# 2024_Nov_24_Esp32.net
KiCad netlist of a schematic drawn in Altium Designer
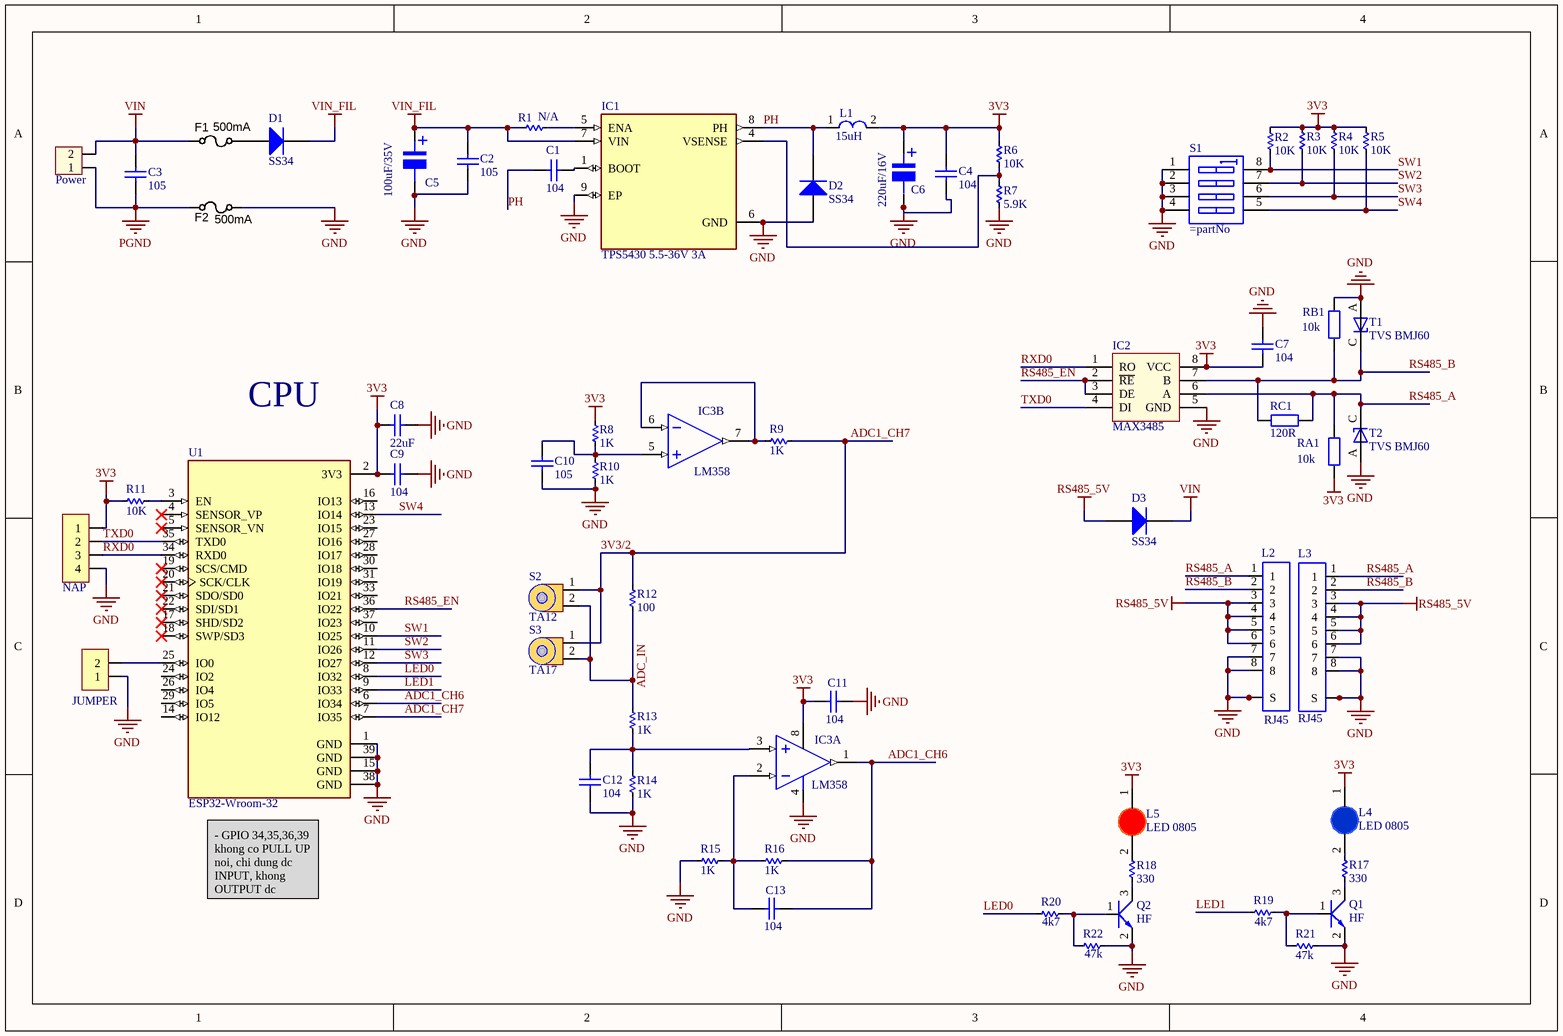
[diagram p0: 2024_Nov_24_Esp32.SchDoc]

(export (version "E")
  (design (tool "Eeschema 10.0.6"))
  (components
    (comp (ref "C1")
      (value "104")
      (footprint "tu 0805")
      (description "Dán")
      (libsource (lib "NGUYEN VAN ANH HaUI") (part "Tu 0805 105 50V 10%"))
    )
    (comp (ref "C2")
      (value "105")
      (footprint "tu 0805")
      (description "Dán")
      (libsource (lib "NGUYEN VAN ANH HaUI") (part "Tu 0805 105 50V 10%"))
    )
    (comp (ref "C3")
      (value "105")
      (footprint "tu 0805")
      (description "Dán")
      (libsource (lib "NGUYEN VAN ANH HaUI") (part "Tu 0805 105 50V 10%"))
    )
    (comp (ref "C4")
      (value "104")
      (footprint "tu 0805")
      (description "Dán")
      (libsource (lib "NGUYEN VAN ANH HaUI") (part "Tu 0805 105 50V 10%"))
    )
    (comp (ref "C5")
      (value "100uF/35V")
      (footprint "tu nhom 8 (f)")
      (description "Dán")
      (libsource (lib "NGUYEN VAN ANH HaUI") (part "Tu Nhom 100uF 50V"))
    )
    (comp (ref "C6")
      (value "220uF/16V")
      (footprint "tu nhom 6.3 (d)")
      (description "Dán")
      (libsource (lib "NGUYEN VAN ANH HaUI") (part "Tu Nhom 220uF 16V"))
    )
    (comp (ref "C7")
      (value "104")
      (footprint "tu 0805")
      (description "Dán")
      (libsource (lib "Altium_Lib_by_KhueNguyenCreator") (part "Tu 0805 104 50V 10%"))
    )
    (comp (ref "C8")
      (value "22uF")
      (footprint "tu 0805")
      (description "Dán")
      (libsource (lib "Altium_Lib_by_KhueNguyenCreator") (part "Tu 0805 105 50V 10%"))
    )
    (comp (ref "C9")
      (value "104")
      (footprint "tu 0805")
      (description "Dán")
      (libsource (lib "Altium_Lib_by_KhueNguyenCreator") (part "Tu 0805 105 50V 10%"))
    )
    (comp (ref "C10")
      (value "105")
      (footprint "tu 0805")
      (description "Dán")
      (libsource (lib "NGUYEN VAN ANH HaUI") (part "Tu 0805 105 50V 10%"))
    )
    (comp (ref "C11")
      (value "104")
      (footprint "tu 0805")
      (description "Dán")
      (libsource (lib "NGUYEN VAN ANH HaUI") (part "Tu 0805 105 50V 10%"))
    )
    (comp (ref "C12")
      (value "104")
      (footprint "tu 0805")
      (description "Dán")
      (libsource (lib "NGUYEN VAN ANH HaUI") (part "Tu 0805 105 50V 10%"))
    )
    (comp (ref "C13")
      (value "104")
      (footprint "tu 0805")
      (description "Dán")
      (libsource (lib "NGUYEN VAN ANH HaUI") (part "Tu 0805 105 50V 10%"))
    )
    (comp (ref "D1")
      (value "SS34")
      (footprint "DIODE SMA")
      (description "Dán")
      (libsource (lib "NGUYEN VAN ANH HaUI") (part "Diode SS34 ( 1N5822 )"))
    )
    (comp (ref "D2")
      (value "SS34")
      (footprint "DIODE SMA")
      (description "Dán")
      (libsource (lib "NGUYEN VAN ANH HaUI") (part "Diode SS34 ( 1N5822 )"))
    )
    (comp (ref "D3")
      (value "SS34")
      (footprint "DIODE SMA")
      (description "Dán")
      (libsource (lib "NGUYEN VAN ANH HaUI") (part "Diode SS34 ( 1N5822 )"))
    )
    (comp (ref "F1")
      (value "500mA")
      (footprint "TU 0805")
      (description "Fuse 500mA 32VDC 0603 SMD")
      (fields (field (name "Comment") "Fast Acting"))
      (libsource (lib "My library altium") (part "FUSE_FAST_500mA_0603"))
    )
    (comp (ref "F2")
      (value "500mA")
      (footprint "TU 0805")
      (description "Fuse 500mA 32VDC 0603 SMD")
      (fields (field (name "Comment") "Fast Acting"))
      (libsource (lib "My library altium") (part "FUSE_FAST_500mA_0603"))
    )
    (comp (ref "H1")
      (value "Power")
      (footprint "XH2.54M-2")
      (description "Cắm")
      (libsource (lib "NGUYEN VAN ANH HaUI") (part "Header 2P 2.54 Duc Thang"))
    )
    (comp (ref "IC1")
      (value "TPS5430 5.5-36V 3A")
      (footprint "TPS5430")
      (libsource (lib "NGUYEN VAN ANH HaUI") (part "TPS5430"))
    )
    (comp (ref "IC2")
      (value "MAX3485")
      (footprint "SOp 8")
      (description "RS232 - RS485 (Same sn75176)")
      (libsource (lib "NGUYEN VAN ANH HaUI") (part "MAX485"))
    )
    (comp (ref "IC3")
      (value "LM358")
      (footprint "SO8")
      (description "Low-Power Dual Operational Amplifier")
      (libsource (lib "NGUYEN VAN ANH HaUI") (part "LM358"))
    )
    (comp (ref "JP1")
      (value "NAP")
      (footprint "JP 1x4 DT")
      (description "Cắm")
      (libsource (lib "NGUYEN VAN ANH HaUI") (part "JP 1x4 2.54 Duc Thang"))
    )
    (comp (ref "JP2")
      (value "JUMPER")
      (footprint "JP 1x2 DT")
      (description "Cắm")
      (libsource (lib "NGUYEN VAN ANH HaUI") (part "JP 1x2 2.54 Duc Thang"))
    )
    (comp (ref "L1")
      (value "15uH")
      (footprint "L-SMD-M-7.3x4.5")
      (fields
        (field (name "PARTNO") "78477010")
        (field (name "MANUFACTURER") "Wurth Elektronik")
        (field (name "CREATED BY") "Baojun Chen")
      )
      (libsource (lib "NGUYEN VAN ANH HaUI") (part "L-SMD-1"))
    )
    (comp (ref "L2")
      (value "RJ45")
      (footprint "Ethernet HR911105A")
      (libsource (lib "NGUYEN VAN ANH HaUI") (part "Ethernet-LAN"))
    )
    (comp (ref "L3")
      (value "RJ45")
      (footprint "Ethernet HR911105A")
      (libsource (lib "NGUYEN VAN ANH HaUI") (part "Ethernet-LAN"))
    )
    (comp (ref "L4")
      (value "LED 0805")
      (footprint "LED-0805-Blue")
      (description "Dán")
      (libsource (lib "NGUYEN VAN ANH HaUI") (part "LED 0805 Xanh Duong"))
    )
    (comp (ref "L5")
      (value "LED 0805")
      (footprint "LED-0805-Red")
      (description "Dán")
      (libsource (lib "NGUYEN VAN ANH HaUI") (part "LED 0805 Do"))
    )
    (comp (ref "Q1")
      (value "HF")
      (footprint "SOT23")
      (description "NPN transistor")
      (libsource (lib "NGUYEN VAN ANH HaUI") (part "C1815 HF SMD"))
    )
    (comp (ref "Q2")
      (value "HF")
      (footprint "SOT23")
      (description "NPN transistor")
      (libsource (lib "NGUYEN VAN ANH HaUI") (part "C1815 HF SMD"))
    )
    (comp (ref "R1")
      (value "N/A")
      (footprint "RES-SMD-0805")
      (description "Resistor")
      (fields
        (field (name "MANUFACTURER") "Generic Components")
        (field (name "PUBLISHER") "Altium Hobart Technology Centre")
      )
      (libsource (lib "NGUYEN VAN ANH HaUI") (part "Res-SMD"))
    )
    (comp (ref "R2")
      (value "10K")
      (footprint "RES-SMD-0805")
      (description "Resistor")
      (fields
        (field (name "MANUFACTURER") "Generic Components")
        (field (name "PUBLISHER") "Altium Hobart Technology Centre")
      )
      (libsource (lib "NGUYEN VAN ANH HaUI") (part "Res-SMD"))
    )
    (comp (ref "R3")
      (value "10K")
      (footprint "RES-SMD-0805")
      (description "Resistor")
      (fields
        (field (name "MANUFACTURER") "Generic Components")
        (field (name "PUBLISHER") "Altium Hobart Technology Centre")
      )
      (libsource (lib "NGUYEN VAN ANH HaUI") (part "Res-SMD"))
    )
    (comp (ref "R4")
      (value "10K")
      (footprint "RES-SMD-0805")
      (description "Resistor")
      (fields
        (field (name "MANUFACTURER") "Generic Components")
        (field (name "PUBLISHER") "Altium Hobart Technology Centre")
      )
      (libsource (lib "NGUYEN VAN ANH HaUI") (part "Res-SMD"))
    )
    (comp (ref "R5")
      (value "10K")
      (footprint "RES-SMD-0805")
      (description "Resistor")
      (fields
        (field (name "MANUFACTURER") "Generic Components")
        (field (name "PUBLISHER") "Altium Hobart Technology Centre")
      )
      (libsource (lib "NGUYEN VAN ANH HaUI") (part "Res-SMD"))
    )
    (comp (ref "R6")
      (value "10K")
      (footprint "RES-SMD-0805")
      (description "Resistor")
      (fields
        (field (name "MANUFACTURER") "Generic Components")
        (field (name "PUBLISHER") "Altium Hobart Technology Centre")
      )
      (libsource (lib "NGUYEN VAN ANH HaUI") (part "Res-SMD"))
    )
    (comp (ref "R7")
      (value "5.9K")
      (footprint "RES-SMD-0805")
      (description "Resistor")
      (fields
        (field (name "MANUFACTURER") "Generic Components")
        (field (name "PUBLISHER") "Altium Hobart Technology Centre")
      )
      (libsource (lib "NGUYEN VAN ANH HaUI") (part "Res-SMD"))
    )
    (comp (ref "R8")
      (value "1K")
      (footprint "RES-SMD-0805")
      (description "Resistor")
      (fields
        (field (name "MANUFACTURER") "Generic Components")
        (field (name "PUBLISHER") "Altium Hobart Technology Centre")
      )
      (libsource (lib "NGUYEN VAN ANH HaUI") (part "Res-SMD"))
    )
    (comp (ref "R9")
      (value "1K")
      (footprint "RES-SMD-0805")
      (description "Resistor")
      (fields
        (field (name "MANUFACTURER") "Generic Components")
        (field (name "PUBLISHER") "Altium Hobart Technology Centre")
      )
      (libsource (lib "NGUYEN VAN ANH HaUI") (part "Res-SMD"))
    )
    (comp (ref "R10")
      (value "1K")
      (footprint "RES-SMD-0805")
      (description "Resistor")
      (fields
        (field (name "MANUFACTURER") "Generic Components")
        (field (name "PUBLISHER") "Altium Hobart Technology Centre")
      )
      (libsource (lib "NGUYEN VAN ANH HaUI") (part "Res-SMD"))
    )
    (comp (ref "R11")
      (value "10K")
      (footprint "RES-SMD-0805")
      (description "Resistor")
      (fields
        (field (name "MANUFACTURER") "Generic Components")
        (field (name "PUBLISHER") "Altium Hobart Technology Centre")
      )
      (libsource (lib "NGUYEN VAN ANH HaUI") (part "Res-SMD"))
    )
    (comp (ref "R12")
      (value "100")
      (footprint "RES-SMD-0805")
      (description "Resistor")
      (fields
        (field (name "MANUFACTURER") "Generic Components")
        (field (name "PUBLISHER") "Altium Hobart Technology Centre")
      )
      (libsource (lib "NGUYEN VAN ANH HaUI") (part "Res-SMD"))
    )
    (comp (ref "R13")
      (value "1K")
      (footprint "RES-SMD-0805")
      (description "Resistor")
      (fields
        (field (name "MANUFACTURER") "Generic Components")
        (field (name "PUBLISHER") "Altium Hobart Technology Centre")
      )
      (libsource (lib "NGUYEN VAN ANH HaUI") (part "Res-SMD"))
    )
    (comp (ref "R14")
      (value "1K")
      (footprint "RES-SMD-0805")
      (description "Resistor")
      (fields
        (field (name "MANUFACTURER") "Generic Components")
        (field (name "PUBLISHER") "Altium Hobart Technology Centre")
      )
      (libsource (lib "NGUYEN VAN ANH HaUI") (part "Res-SMD"))
    )
    (comp (ref "R15")
      (value "1K")
      (footprint "RES-SMD-0805")
      (description "Resistor")
      (fields
        (field (name "MANUFACTURER") "Generic Components")
        (field (name "PUBLISHER") "Altium Hobart Technology Centre")
      )
      (libsource (lib "NGUYEN VAN ANH HaUI") (part "Res-SMD"))
    )
    (comp (ref "R16")
      (value "1K")
      (footprint "RES-SMD-0805")
      (description "Resistor")
      (fields
        (field (name "MANUFACTURER") "Generic Components")
        (field (name "PUBLISHER") "Altium Hobart Technology Centre")
      )
      (libsource (lib "NGUYEN VAN ANH HaUI") (part "Res-SMD"))
    )
    (comp (ref "R17")
      (value "330")
      (footprint "RES-SMD-0805")
      (description "Resistor")
      (fields
        (field (name "MANUFACTURER") "Generic Components")
        (field (name "PUBLISHER") "Altium Hobart Technology Centre")
      )
      (libsource (lib "NGUYEN VAN ANH HaUI") (part "Res-SMD"))
    )
    (comp (ref "R18")
      (value "330")
      (footprint "RES-SMD-0805")
      (description "Resistor")
      (fields
        (field (name "MANUFACTURER") "Generic Components")
        (field (name "PUBLISHER") "Altium Hobart Technology Centre")
      )
      (libsource (lib "NGUYEN VAN ANH HaUI") (part "Res-SMD"))
    )
    (comp (ref "R19")
      (value "4k7")
      (footprint "RES-SMD-0805")
      (description "Resistor")
      (fields
        (field (name "MANUFACTURER") "Generic Components")
        (field (name "PUBLISHER") "Altium Hobart Technology Centre")
      )
      (libsource (lib "NGUYEN VAN ANH HaUI") (part "Res-SMD"))
    )
    (comp (ref "R20")
      (value "4k7")
      (footprint "RES-SMD-0805")
      (description "Resistor")
      (fields
        (field (name "MANUFACTURER") "Generic Components")
        (field (name "PUBLISHER") "Altium Hobart Technology Centre")
      )
      (libsource (lib "NGUYEN VAN ANH HaUI") (part "Res-SMD"))
    )
    (comp (ref "R21")
      (value "47k")
      (footprint "RES-SMD-0805")
      (description "Resistor")
      (fields
        (field (name "MANUFACTURER") "Generic Components")
        (field (name "PUBLISHER") "Altium Hobart Technology Centre")
      )
      (libsource (lib "NGUYEN VAN ANH HaUI") (part "Res-SMD"))
    )
    (comp (ref "R22")
      (value "47k")
      (footprint "RES-SMD-0805")
      (description "Resistor")
      (fields
        (field (name "MANUFACTURER") "Generic Components")
        (field (name "PUBLISHER") "Altium Hobart Technology Centre")
      )
      (libsource (lib "NGUYEN VAN ANH HaUI") (part "Res-SMD"))
    )
    (comp (ref "RA1")
      (value "10k")
      (footprint "SM-RES-0805")
      (description "Resistor 1/4W")
      (libsource (lib "syhaunguyen") (part "R1/4W"))
    )
    (comp (ref "RB1")
      (value "10k")
      (footprint "SM-RES-0805")
      (description "Resistor 1/4W")
      (libsource (lib "syhaunguyen") (part "R1/4W"))
    )
    (comp (ref "RC1")
      (value "120R")
      (footprint "SM-RES-0805")
      (description "Resistor 1/4W")
      (libsource (lib "syhaunguyen") (part "R1/4W"))
    )
    (comp (ref "S1")
      (value "~")
      (footprint "SW-DIP4")
      (description "WS-DITV 2.54 mm small compact THT flat actuator with top tape")
      (fields
        (field (name "MANUFACTURER") "Wurth Elektronik")
        (field (name "PART NO.") "418127160904")
        (field (name "CREATED BY") "Baojun Chen")
      )
      (libsource (lib "NGUYEN VAN ANH HaUI") (part "SWDIP4"))
    )
    (comp (ref "S2") (value "TA12") (footprint "TA12") (libsource (lib "NGUYEN VAN ANH HaUI") (part "TA12")))
    (comp (ref "S3") (value "TA17") (footprint "TA12") (libsource (lib "NGUYEN VAN ANH HaUI") (part "TA12")))
    (comp (ref "T1")
      (value "TVS BMJ60")
      (footprint "TVS BMJ60")
      (libsource (lib "NGUYEN VAN ANH HaUI") (part "TVS BMJ60"))
    )
    (comp (ref "T2")
      (value "TVS BMJ60")
      (footprint "TVS BMJ60")
      (libsource (lib "NGUYEN VAN ANH HaUI") (part "TVS BMJ60"))
    )
    (comp (ref "U1")
      (value "ESP32-Wroom-32")
      (footprint "ESP32-Wroom-32")
      (libsource (lib "NGUYEN VAN ANH HaUI") (part "ESP32-Wroom-32"))
    )
  )
  (nets
    (net (code "1") (name "/3V3{slash}2") (class "Default")
      (node (ref "R12") (pin "1") (pinfunction "1_1") (pintype "passive"))
      (node (ref "R9") (pin "2") (pinfunction "2_2") (pintype "passive"))
      (node (ref "S2") (pin "1") (pinfunction "0_1") (pintype "passive"))
      (node (ref "S3") (pin "1") (pinfunction "0_1") (pintype "passive"))
      (node (ref "U1") (pin "7") (pinfunction "IO35_7") (pintype "bidirectional"))
    )
    (net (code "2") (name "/ADC1_CH6") (class "Default")
      (node (ref "C13") (pin "1") (pinfunction "1_1") (pintype "passive"))
      (node (ref "IC3") (pin "1") (pinfunction "OUT_1") (pintype "output"))
      (node (ref "R16") (pin "2") (pinfunction "2_2") (pintype "passive"))
      (node (ref "U1") (pin "6") (pinfunction "IO34_6") (pintype "bidirectional"))
    )
    (net (code "3") (name "/ADC_IN") (class "Default")
      (node (ref "R12") (pin "2") (pinfunction "2_2") (pintype "passive"))
      (node (ref "R13") (pin "1") (pinfunction "1_1") (pintype "passive"))
      (node (ref "S2") (pin "2") (pinfunction "1_2") (pintype "passive"))
      (node (ref "S3") (pin "2") (pinfunction "1_2") (pintype "passive"))
    )
    (net (code "4") (name "/LED0") (class "Default")
      (node (ref "R20") (pin "2") (pinfunction "2_2") (pintype "passive"))
      (node (ref "U1") (pin "8") (pinfunction "IO32_8") (pintype "bidirectional"))
    )
    (net (code "5") (name "/LED1") (class "Default")
      (node (ref "R19") (pin "2") (pinfunction "2_2") (pintype "passive"))
      (node (ref "U1") (pin "9") (pinfunction "IO33_9") (pintype "bidirectional"))
    )
    (net (code "6") (name "/PH") (class "Default")
      (node (ref "C1") (pin "1") (pinfunction "1_1") (pintype "passive"))
      (node (ref "D2") (pin "2") (pinfunction "K_2") (pintype "passive"))
      (node (ref "IC1") (pin "8") (pinfunction "PH_8") (pintype "output"))
      (node (ref "L1") (pin "1") (pinfunction "1_1") (pintype "passive"))
    )
    (net (code "7") (name "/RS485_A") (class "Default")
      (node (ref "IC2") (pin "6") (pinfunction "A_6") (pintype "passive"))
      (node (ref "L2") (pin "1") (pinfunction "1_1") (pintype "passive"))
      (node (ref "L3") (pin "1") (pinfunction "1_1") (pintype "passive"))
      (node (ref "RA1") (pin "2") (pinfunction "2_2") (pintype "passive"))
      (node (ref "RC1") (pin "1") (pinfunction "1_1") (pintype "passive"))
      (node (ref "T2") (pin "C") (pinfunction "C_C") (pintype "passive"))
    )
    (net (code "8") (name "/RS485_B") (class "Default")
      (node (ref "IC2") (pin "7") (pinfunction "B_7") (pintype "passive"))
      (node (ref "L2") (pin "2") (pinfunction "2_2") (pintype "passive"))
      (node (ref "L3") (pin "2") (pinfunction "2_2") (pintype "passive"))
      (node (ref "RB1") (pin "1") (pinfunction "1_1") (pintype "passive"))
      (node (ref "RC1") (pin "2") (pinfunction "2_2") (pintype "passive"))
      (node (ref "T1") (pin "C") (pinfunction "C_C") (pintype "passive"))
    )
    (net (code "9") (name "/RS485_EN") (class "Default")
      (node (ref "IC2") (pin "2") (pinfunction "~{RE}_2") (pintype "passive"))
      (node (ref "IC2") (pin "3") (pinfunction "DE_3") (pintype "passive"))
      (node (ref "U1") (pin "36") (pinfunction "IO22_36") (pintype "bidirectional"))
    )
    (net (code "10") (name "/RXD0") (class "Default")
      (node (ref "IC2") (pin "1") (pinfunction "RO_1") (pintype "passive"))
      (node (ref "JP1") (pin "3") (pinfunction "3_3") (pintype "passive"))
      (node (ref "U1") (pin "34") (pinfunction "RXD0_34") (pintype "bidirectional"))
    )
    (net (code "11") (name "/SW1") (class "Default")
      (node (ref "R2") (pin "1") (pinfunction "1_1") (pintype "passive"))
      (node (ref "S1") (pin "8") (pinfunction "8_8") (pintype "passive"))
      (node (ref "U1") (pin "10") (pinfunction "IO25_10") (pintype "bidirectional"))
    )
    (net (code "12") (name "/SW2") (class "Default")
      (node (ref "R3") (pin "1") (pinfunction "1_1") (pintype "passive"))
      (node (ref "S1") (pin "7") (pinfunction "7_7") (pintype "passive"))
      (node (ref "U1") (pin "11") (pinfunction "IO26_11") (pintype "bidirectional"))
    )
    (net (code "13") (name "/SW3") (class "Default")
      (node (ref "R4") (pin "1") (pinfunction "1_1") (pintype "passive"))
      (node (ref "S1") (pin "6") (pinfunction "6_6") (pintype "passive"))
      (node (ref "U1") (pin "12") (pinfunction "IO27_12") (pintype "bidirectional"))
    )
    (net (code "14") (name "/SW4") (class "Default")
      (node (ref "R5") (pin "1") (pinfunction "1_1") (pintype "passive"))
      (node (ref "S1") (pin "5") (pinfunction "5_5") (pintype "passive"))
      (node (ref "U1") (pin "13") (pinfunction "IO14_13") (pintype "bidirectional"))
    )
    (net (code "15") (name "/TXD0") (class "Default")
      (node (ref "IC2") (pin "4") (pinfunction "DI_4") (pintype "passive"))
      (node (ref "JP1") (pin "2") (pinfunction "2_2") (pintype "passive"))
      (node (ref "U1") (pin "35") (pinfunction "TXD0_35") (pintype "bidirectional"))
    )
    (net (code "16") (name "3V3") (class "Default")
      (node (ref "C11") (pin "2") (pinfunction "2_2") (pintype "passive"))
      (node (ref "C4") (pin "2") (pinfunction "2_2") (pintype "passive"))
      (node (ref "C6") (pin "1") (pinfunction "1_1") (pintype "passive"))
      (node (ref "C7") (pin "1") (pinfunction "1_1") (pintype "passive"))
      (node (ref "C8") (pin "2") (pinfunction "2_2") (pintype "passive"))
      (node (ref "C9") (pin "2") (pinfunction "2_2") (pintype "passive"))
      (node (ref "IC2") (pin "8") (pinfunction "VCC_8") (pintype "passive"))
      (node (ref "IC3") (pin "8") (pinfunction "+V_8") (pintype "passive"))
      (node (ref "JP1") (pin "1") (pinfunction "1_1") (pintype "passive"))
      (node (ref "L1") (pin "2") (pinfunction "2_2") (pintype "passive"))
      (node (ref "L4") (pin "1") (pinfunction "A_1") (pintype "passive"))
      (node (ref "L5") (pin "1") (pinfunction "A_1") (pintype "passive"))
      (node (ref "R11") (pin "1") (pinfunction "1_1") (pintype "passive"))
      (node (ref "R2") (pin "2") (pinfunction "2_2") (pintype "passive"))
      (node (ref "R3") (pin "2") (pinfunction "2_2") (pintype "passive"))
      (node (ref "R4") (pin "2") (pinfunction "2_2") (pintype "passive"))
      (node (ref "R5") (pin "2") (pinfunction "2_2") (pintype "passive"))
      (node (ref "R6") (pin "1") (pinfunction "1_1") (pintype "passive"))
      (node (ref "R8") (pin "1") (pinfunction "1_1") (pintype "passive"))
      (node (ref "RA1") (pin "1") (pinfunction "1_1") (pintype "passive"))
      (node (ref "U1") (pin "2") (pinfunction "3V3_2") (pintype "power_in"))
    )
    (net (code "17") (name "GND") (class "Default")
      (node (ref "C10") (pin "2") (pinfunction "2_2") (pintype "passive"))
      (node (ref "C11") (pin "1") (pinfunction "1_1") (pintype "passive"))
      (node (ref "C12") (pin "1") (pinfunction "1_1") (pintype "passive"))
      (node (ref "C2") (pin "2") (pinfunction "2_2") (pintype "passive"))
      (node (ref "C4") (pin "1") (pinfunction "1_1") (pintype "passive"))
      (node (ref "C5") (pin "2") (pinfunction "2_2") (pintype "passive"))
      (node (ref "C6") (pin "2") (pinfunction "2_2") (pintype "passive"))
      (node (ref "C7") (pin "2") (pinfunction "2_2") (pintype "passive"))
      (node (ref "C8") (pin "1") (pinfunction "1_1") (pintype "passive"))
      (node (ref "C9") (pin "1") (pinfunction "1_1") (pintype "passive"))
      (node (ref "D2") (pin "1") (pinfunction "A_1") (pintype "passive"))
      (node (ref "F2") (pin "2") (pinfunction "2_2") (pintype "passive"))
      (node (ref "IC1") (pin "6") (pinfunction "GND_6") (pintype "power_in"))
      (node (ref "IC1") (pin "9") (pinfunction "EP_9") (pintype "bidirectional"))
      (node (ref "IC2") (pin "5") (pinfunction "GND_5") (pintype "passive"))
      (node (ref "IC3") (pin "4") (pinfunction "-V_4") (pintype "passive"))
      (node (ref "JP1") (pin "4") (pinfunction "4_4") (pintype "passive"))
      (node (ref "JP2") (pin "1") (pinfunction "1_1") (pintype "passive"))
      (node (ref "L2") (pin "7") (pinfunction "7_7") (pintype "passive"))
      (node (ref "L2") (pin "8") (pinfunction "8_8") (pintype "passive"))
      (node (ref "L2") (pin "S1") (pinfunction "S_S1") (pintype "passive"))
      (node (ref "L2") (pin "S2") (pinfunction "S_S2") (pintype "passive"))
      (node (ref "L3") (pin "7") (pinfunction "7_7") (pintype "passive"))
      (node (ref "L3") (pin "8") (pinfunction "8_8") (pintype "passive"))
      (node (ref "L3") (pin "S1") (pinfunction "S_S1") (pintype "passive"))
      (node (ref "L3") (pin "S2") (pinfunction "S_S2") (pintype "passive"))
      (node (ref "Q1") (pin "2") (pinfunction "E_2") (pintype "passive"))
      (node (ref "Q2") (pin "2") (pinfunction "E_2") (pintype "passive"))
      (node (ref "R10") (pin "2") (pinfunction "2_2") (pintype "passive"))
      (node (ref "R14") (pin "2") (pinfunction "2_2") (pintype "passive"))
      (node (ref "R15") (pin "1") (pinfunction "1_1") (pintype "passive"))
      (node (ref "R21") (pin "1") (pinfunction "1_1") (pintype "passive"))
      (node (ref "R22") (pin "1") (pinfunction "1_1") (pintype "passive"))
      (node (ref "R7") (pin "2") (pinfunction "2_2") (pintype "passive"))
      (node (ref "RB1") (pin "2") (pinfunction "2_2") (pintype "passive"))
      (node (ref "S1") (pin "1") (pinfunction "1_1") (pintype "passive"))
      (node (ref "S1") (pin "2") (pinfunction "2_2") (pintype "passive"))
      (node (ref "S1") (pin "3") (pinfunction "3_3") (pintype "passive"))
      (node (ref "S1") (pin "4") (pinfunction "4_4") (pintype "passive"))
      (node (ref "T1") (pin "A") (pinfunction "A_A") (pintype "passive"))
      (node (ref "T2") (pin "A") (pinfunction "A_A") (pintype "passive"))
      (node (ref "U1") (pin "1") (pinfunction "GND_1") (pintype "power_in"))
      (node (ref "U1") (pin "15") (pinfunction "GND_15") (pintype "power_in"))
      (node (ref "U1") (pin "38") (pinfunction "GND_38") (pintype "power_in"))
      (node (ref "U1") (pin "39") (pinfunction "GND_39") (pintype "power_in"))
    )
    (net (code "18") (name "Net-(D1-A)") (class "Default")
      (node (ref "D1") (pin "1") (pinfunction "A_1") (pintype "passive"))
      (node (ref "F1") (pin "2") (pinfunction "2_2") (pintype "passive"))
    )
    (net (code "19") (name "Net-(IC1-BOOT)") (class "Default")
      (node (ref "C1") (pin "2") (pinfunction "2_2") (pintype "passive"))
      (node (ref "IC1") (pin "1") (pinfunction "BOOT_1") (pintype "bidirectional"))
    )
    (net (code "20") (name "Net-(IC1-ENA)") (class "Default")
      (node (ref "IC1") (pin "5") (pinfunction "ENA_5") (pintype "input"))
      (node (ref "R1") (pin "1") (pinfunction "1_1") (pintype "passive"))
    )
    (net (code "21") (name "Net-(IC1-VSENSE)") (class "Default")
      (node (ref "IC1") (pin "4") (pinfunction "VSENSE_4") (pintype "output"))
      (node (ref "R6") (pin "2") (pinfunction "2_2") (pintype "passive"))
      (node (ref "R7") (pin "1") (pinfunction "1_1") (pintype "passive"))
    )
    (net (code "22") (name "Net-(IC3A-IN+)") (class "Default")
      (node (ref "C12") (pin "2") (pinfunction "2_2") (pintype "passive"))
      (node (ref "IC3") (pin "3") (pinfunction "IN+_3") (pintype "input"))
      (node (ref "R13") (pin "2") (pinfunction "2_2") (pintype "passive"))
      (node (ref "R14") (pin "1") (pinfunction "1_1") (pintype "passive"))
    )
    (net (code "23") (name "Net-(IC3A-IN-)") (class "Default")
      (node (ref "C13") (pin "2") (pinfunction "2_2") (pintype "passive"))
      (node (ref "IC3") (pin "2") (pinfunction "IN-_2") (pintype "input"))
      (node (ref "R15") (pin "2") (pinfunction "2_2") (pintype "passive"))
      (node (ref "R16") (pin "1") (pinfunction "1_1") (pintype "passive"))
    )
    (net (code "24") (name "Net-(IC3B-IN+)") (class "Default")
      (node (ref "C10") (pin "1") (pinfunction "1_1") (pintype "passive"))
      (node (ref "IC3") (pin "5") (pinfunction "IN+_5") (pintype "input"))
      (node (ref "R10") (pin "1") (pinfunction "1_1") (pintype "passive"))
      (node (ref "R8") (pin "2") (pinfunction "2_2") (pintype "passive"))
    )
    (net (code "25") (name "Net-(IC3B-IN-)") (class "Default")
      (node (ref "IC3") (pin "6") (pinfunction "IN-_6") (pintype "input"))
      (node (ref "IC3") (pin "7") (pinfunction "OUT_7") (pintype "output"))
      (node (ref "R9") (pin "1") (pinfunction "1_1") (pintype "passive"))
    )
    (net (code "26") (name "Net-(L4-K)") (class "Default")
      (node (ref "L4") (pin "2") (pinfunction "K_2") (pintype "passive"))
      (node (ref "R17") (pin "2") (pinfunction "2_2") (pintype "passive"))
    )
    (net (code "27") (name "Net-(L5-K)") (class "Default")
      (node (ref "L5") (pin "2") (pinfunction "K_2") (pintype "passive"))
      (node (ref "R18") (pin "2") (pinfunction "2_2") (pintype "passive"))
    )
    (net (code "28") (name "Net-(Q1-B)") (class "Default")
      (node (ref "Q1") (pin "1") (pinfunction "B_1") (pintype "passive"))
      (node (ref "R19") (pin "1") (pinfunction "1_1") (pintype "passive"))
      (node (ref "R21") (pin "2") (pinfunction "2_2") (pintype "passive"))
    )
    (net (code "29") (name "Net-(Q1-C)") (class "Default")
      (node (ref "Q1") (pin "3") (pinfunction "C_3") (pintype "passive"))
      (node (ref "R17") (pin "1") (pinfunction "1_1") (pintype "passive"))
    )
    (net (code "30") (name "Net-(Q2-B)") (class "Default")
      (node (ref "Q2") (pin "1") (pinfunction "B_1") (pintype "passive"))
      (node (ref "R20") (pin "1") (pinfunction "1_1") (pintype "passive"))
      (node (ref "R22") (pin "2") (pinfunction "2_2") (pintype "passive"))
    )
    (net (code "31") (name "Net-(Q2-C)") (class "Default")
      (node (ref "Q2") (pin "3") (pinfunction "C_3") (pintype "passive"))
      (node (ref "R18") (pin "1") (pinfunction "1_1") (pintype "passive"))
    )
    (net (code "32") (name "Net-(U1-EN)") (class "Default")
      (node (ref "R11") (pin "2") (pinfunction "2_2") (pintype "passive"))
      (node (ref "U1") (pin "3") (pinfunction "EN_3") (pintype "input"))
    )
    (net (code "33") (name "Net-(U1-IO0)") (class "Default")
      (node (ref "JP2") (pin "2") (pinfunction "2_2") (pintype "passive"))
      (node (ref "U1") (pin "25") (pinfunction "IO0_25") (pintype "bidirectional"))
    )
    (net (code "34") (name "PGND") (class "Default")
      (node (ref "C3") (pin "2") (pinfunction "2_2") (pintype "passive"))
      (node (ref "F2") (pin "1") (pinfunction "1_1") (pintype "passive"))
      (node (ref "H1") (pin "1") (pinfunction "1_1") (pintype "passive"))
    )
    (net (code "35") (name "RS485_5V") (class "Default")
      (node (ref "D3") (pin "1") (pinfunction "A_1") (pintype "passive"))
      (node (ref "L2") (pin "3") (pinfunction "3_3") (pintype "passive"))
      (node (ref "L2") (pin "4") (pinfunction "4_4") (pintype "passive"))
      (node (ref "L2") (pin "5") (pinfunction "5_5") (pintype "passive"))
      (node (ref "L2") (pin "6") (pinfunction "6_6") (pintype "passive"))
      (node (ref "L3") (pin "3") (pinfunction "3_3") (pintype "passive"))
      (node (ref "L3") (pin "4") (pinfunction "4_4") (pintype "passive"))
      (node (ref "L3") (pin "5") (pinfunction "5_5") (pintype "passive"))
      (node (ref "L3") (pin "6") (pinfunction "6_6") (pintype "passive"))
    )
    (net (code "36") (name "VIN") (class "Default")
      (node (ref "C3") (pin "1") (pinfunction "1_1") (pintype "passive"))
      (node (ref "D3") (pin "2") (pinfunction "K_2") (pintype "passive"))
      (node (ref "F1") (pin "1") (pinfunction "1_1") (pintype "passive"))
      (node (ref "H1") (pin "2") (pinfunction "2_2") (pintype "passive"))
    )
    (net (code "37") (name "VIN_FIL") (class "Default")
      (node (ref "C2") (pin "1") (pinfunction "1_1") (pintype "passive"))
      (node (ref "C5") (pin "1") (pinfunction "1_1") (pintype "passive"))
      (node (ref "D1") (pin "2") (pinfunction "K_2") (pintype "passive"))
      (node (ref "IC1") (pin "7") (pinfunction "VIN_7") (pintype "input"))
      (node (ref "R1") (pin "2") (pinfunction "2_2") (pintype "passive"))
    )
    (net (code "38") (name "unconnected-(U1-IO2-Pad24)") (class "Default")
      (node (ref "U1") (pin "24") (pinfunction "IO2_24") (pintype "bidirectional"))
    )
    (net (code "39") (name "unconnected-(U1-IO4-Pad26)") (class "Default")
      (node (ref "U1") (pin "26") (pinfunction "IO4_26") (pintype "bidirectional"))
    )
    (net (code "40") (name "unconnected-(U1-IO5-Pad29)") (class "Default")
      (node (ref "U1") (pin "29") (pinfunction "IO5_29") (pintype "bidirectional"))
    )
    (net (code "41") (name "unconnected-(U1-IO12-Pad14)") (class "Default")
      (node (ref "U1") (pin "14") (pinfunction "IO12_14") (pintype "bidirectional"))
    )
    (net (code "42") (name "unconnected-(U1-IO13-Pad16)") (class "Default")
      (node (ref "U1") (pin "16") (pinfunction "IO13_16") (pintype "bidirectional"))
    )
    (net (code "43") (name "unconnected-(U1-IO15-Pad23)") (class "Default")
      (node (ref "U1") (pin "23") (pinfunction "IO15_23") (pintype "bidirectional"))
    )
    (net (code "44") (name "unconnected-(U1-IO16-Pad27)") (class "Default")
      (node (ref "U1") (pin "27") (pinfunction "IO16_27") (pintype "bidirectional"))
    )
    (net (code "45") (name "unconnected-(U1-IO17-Pad28)") (class "Default")
      (node (ref "U1") (pin "28") (pinfunction "IO17_28") (pintype "bidirectional"))
    )
    (net (code "46") (name "unconnected-(U1-IO18-Pad30)") (class "Default")
      (node (ref "U1") (pin "30") (pinfunction "IO18_30") (pintype "bidirectional"))
    )
    (net (code "47") (name "unconnected-(U1-IO19-Pad31)") (class "Default")
      (node (ref "U1") (pin "31") (pinfunction "IO19_31") (pintype "bidirectional"))
    )
    (net (code "48") (name "unconnected-(U1-IO21-Pad33)") (class "Default")
      (node (ref "U1") (pin "33") (pinfunction "IO21_33") (pintype "bidirectional"))
    )
    (net (code "49") (name "unconnected-(U1-IO23-Pad37)") (class "Default")
      (node (ref "U1") (pin "37") (pinfunction "IO23_37") (pintype "bidirectional"))
    )
    (net (code "50") (name "unconnected-(U1-SCK{slash}CLK-Pad20)") (class "Default")
      (node (ref "U1") (pin "20") (pinfunction "SCK/CLK_20") (pintype "bidirectional+no_connect"))
    )
    (net (code "51") (name "unconnected-(U1-SCS{slash}CMD-Pad19)") (class "Default")
      (node (ref "U1") (pin "19") (pinfunction "SCS/CMD_19") (pintype "bidirectional+no_connect"))
    )
    (net (code "52") (name "unconnected-(U1-SDI{slash}SD1-Pad22)") (class "Default")
      (node (ref "U1") (pin "22") (pinfunction "SDI/SD1_22") (pintype "bidirectional+no_connect"))
    )
    (net (code "53") (name "unconnected-(U1-SDO{slash}SD0-Pad21)") (class "Default")
      (node (ref "U1") (pin "21") (pinfunction "SDO/SD0_21") (pintype "bidirectional+no_connect"))
    )
    (net (code "54") (name "unconnected-(U1-SENSOR_VN-Pad5)") (class "Default")
      (node (ref "U1") (pin "5") (pinfunction "SENSOR_VN_5") (pintype "input+no_connect"))
    )
    (net (code "55") (name "unconnected-(U1-SENSOR_VP-Pad4)") (class "Default")
      (node (ref "U1") (pin "4") (pinfunction "SENSOR_VP_4") (pintype "input+no_connect"))
    )
    (net (code "56") (name "unconnected-(U1-SHD{slash}SD2-Pad17)") (class "Default")
      (node (ref "U1") (pin "17") (pinfunction "SHD/SD2_17") (pintype "bidirectional+no_connect"))
    )
    (net (code "57") (name "unconnected-(U1-SWP{slash}SD3-Pad18)") (class "Default")
      (node (ref "U1") (pin "18") (pinfunction "SWP/SD3_18") (pintype "bidirectional+no_connect"))
    )
  )
)
